# TestPCB_2561.net
KiCad netlist of a schematic drawn in Altium Designer
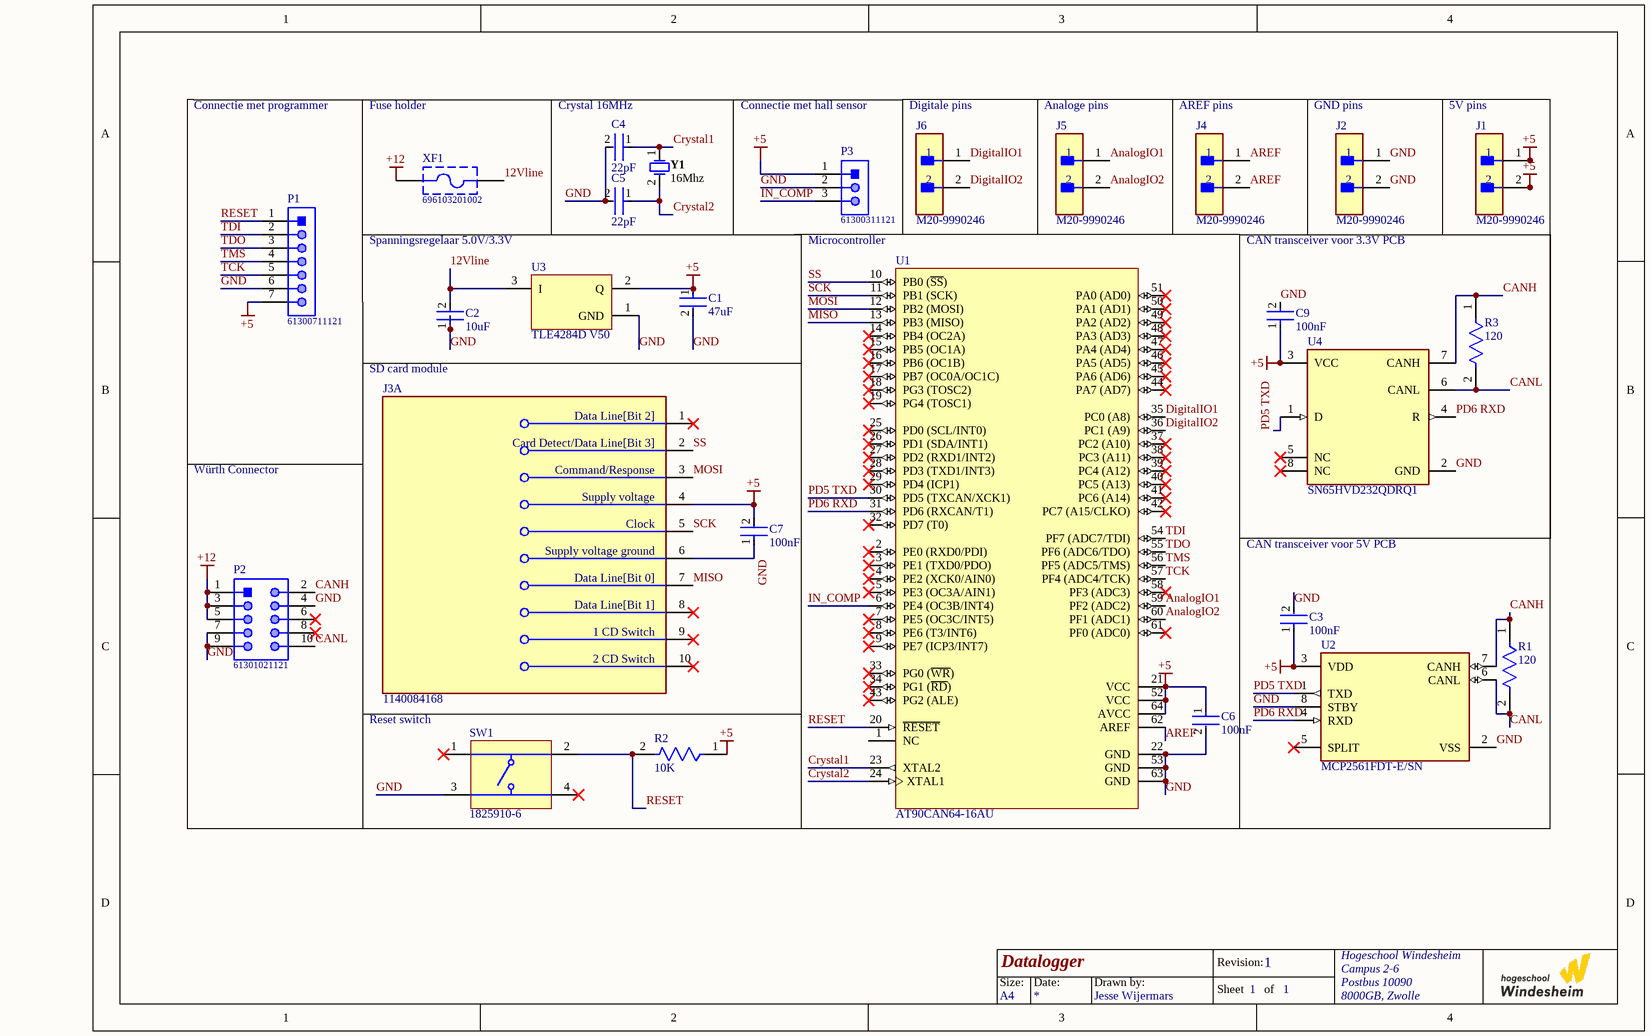
[diagram p0: TestPCB_2561.SchDoc]

(export (version "E")
  (design (tool "Eeschema 10.0.6"))
  (components
    (comp (ref "C1")
      (value "47uF")
      (footprint "FP-CC1206-1_25-MFG")
      (description "CAP CER 0.1UF 50V X7R 1206")
      (fields
        (field (name "OCTOPART") "https://octopart.com/cc1206krx7r9bb104-yageo-39467816")
        (field (name "TOLERANCE") "0.1")
      )
      (libsource (lib "Altium Content Vault") (part "11868f565c42a9108669ba33697ecf6"))
    )
    (comp (ref "C2")
      (value "10uF")
      (footprint "FP-CC1206-1_25-MFG")
      (description "CAP CER 0.1UF 50V X7R 1206")
      (fields
        (field (name "OCTOPART") "https://octopart.com/cc1206krx7r9bb104-yageo-39467816")
        (field (name "TOLERANCE") "0.1")
      )
      (libsource (lib "Altium Content Vault") (part "11868f565c42a9108669ba33697ecf6"))
    )
    (comp (ref "C3")
      (value "100nF")
      (footprint "FP-CC1206-1_25-MFG")
      (description "CAP CER 0.1UF 50V X7R 1206")
      (fields
        (field (name "OCTOPART") "https://octopart.com/cc1206krx7r9bb104-yageo-39467816")
        (field (name "TOLERANCE") "0.1")
      )
      (libsource (lib "Altium Content Vault") (part "11868f565c42a9108669ba33697ecf6"))
    )
    (comp (ref "C4")
      (value "22pF")
      (footprint "FP-CC1206-1_25-MFG")
      (description "CAP CER 0.1UF 50V X7R 1206")
      (fields
        (field (name "OCTOPART") "https://octopart.com/cc1206krx7r9bb104-yageo-39467816")
        (field (name "TOLERANCE") "0.1")
      )
      (libsource (lib "Altium Content Vault") (part "11868f565c42a9108669ba33697ecf6"))
    )
    (comp (ref "C5")
      (value "22pF")
      (footprint "FP-CC1206-1_25-MFG")
      (description "CAP CER 0.1UF 50V X7R 1206")
      (fields
        (field (name "OCTOPART") "https://octopart.com/cc1206krx7r9bb104-yageo-39467816")
        (field (name "TOLERANCE") "0.1")
      )
      (libsource (lib "Altium Content Vault") (part "11868f565c42a9108669ba33697ecf6"))
    )
    (comp (ref "C6")
      (value "100nF")
      (footprint "FP-CC1206-1_25-MFG")
      (description "CAP CER 0.1UF 50V X7R 1206")
      (fields
        (field (name "OCTOPART") "https://octopart.com/cc1206krx7r9bb104-yageo-39467816")
        (field (name "TOLERANCE") "0.1")
      )
      (libsource (lib "Altium Content Vault") (part "11868f565c42a9108669ba33697ecf6"))
    )
    (comp (ref "C7")
      (value "100nF")
      (footprint "FP-CC1206-1_25-MFG")
      (description "CAP CER 0.1UF 50V X7R 1206")
      (fields
        (field (name "OCTOPART") "https://octopart.com/cc1206krx7r9bb104-yageo-39467816")
        (field (name "TOLERANCE") "0.1")
      )
      (libsource (lib "Altium Content Vault") (part "11868f565c42a9108669ba33697ecf6"))
    )
    (comp (ref "C9")
      (value "100nF")
      (footprint "FP-CC1206-1_25-MFG")
      (description "CAP CER 0.1UF 50V X7R 1206")
      (fields
        (field (name "OCTOPART") "https://octopart.com/cc1206krx7r9bb104-yageo-39467816")
        (field (name "TOLERANCE") "0.1")
      )
      (libsource (lib "Altium Content Vault") (part "11868f565c42a9108669ba33697ecf6"))
    )
    (comp (ref "J1")
      (value "M20-9990246")
      (footprint "FP-M20-9990246-MFG")
      (description "CONN HEADER VERT 2POS 2.54MM")
      (fields
        (field (name "OCTOPART") "https://octopart.com/m20-9990246-harwin-2590635")
        (field (name "MANUFACTURER") "Harwin")
      )
      (libsource (lib "Altium Content Vault") (part "3bc925449376181038e59eaffc5286c"))
    )
    (comp (ref "J2")
      (value "M20-9990246")
      (footprint "FP-M20-9990246-MFG")
      (description "CONN HEADER VERT 2POS 2.54MM")
      (fields
        (field (name "OCTOPART") "https://octopart.com/m20-9990246-harwin-2590635")
        (field (name "MANUFACTURER") "Harwin")
      )
      (libsource (lib "Altium Content Vault") (part "3bc925449376181038e59eaffc5286c"))
    )
    (comp (ref "J3")
      (value "1140084168")
      (footprint "FP-1140084168-0")
      (description "CONN MICRO SD CARD PUSH-PULL R/A")
      (libsource (lib "Altium Content Vault") (part "4825e9221753844f043cd0795554885"))
    )
    (comp (ref "J4")
      (value "M20-9990246")
      (footprint "FP-M20-9990246-MFG")
      (description "CONN HEADER VERT 2POS 2.54MM")
      (fields
        (field (name "OCTOPART") "https://octopart.com/m20-9990246-harwin-2590635")
        (field (name "MANUFACTURER") "Harwin")
      )
      (libsource (lib "Altium Content Vault") (part "3bc925449376181038e59eaffc5286c"))
    )
    (comp (ref "J5")
      (value "M20-9990246")
      (footprint "FP-M20-9990246-MFG")
      (description "CONN HEADER VERT 2POS 2.54MM")
      (fields
        (field (name "OCTOPART") "https://octopart.com/m20-9990246-harwin-2590635")
        (field (name "MANUFACTURER") "Harwin")
      )
      (libsource (lib "Altium Content Vault") (part "3bc925449376181038e59eaffc5286c"))
    )
    (comp (ref "J6")
      (value "M20-9990246")
      (footprint "FP-M20-9990246-MFG")
      (description "CONN HEADER VERT 2POS 2.54MM")
      (fields
        (field (name "OCTOPART") "https://octopart.com/m20-9990246-harwin-2590635")
        (field (name "MANUFACTURER") "Harwin")
      )
      (libsource (lib "Altium Content Vault") (part "3bc925449376181038e59eaffc5286c"))
    )
    (comp (ref "P1")
      (value "61300711121")
      (footprint "61300711121")
      (description "THT Vertical Pin Header WR-PHD, Pitch 2.54 mm, Single Row, 7 pins")
      (fields (field (name "MANUFACTURER") "Wurth Elektronik") (field (name "PUBLISHER") "WurthElektronik"))
      (libsource (lib "Altium Content Vault") (part "WE-CN-1P-M-R7"))
    )
    (comp (ref "P2")
      (value "61301021121")
      (footprint "61301021121")
      (description "THT Vertical Pin Header WR-PHD, Pitch 2.54 mm, Dual Row, 10 pins")
      (fields (field (name "MANUFACTURER") "Wurth Elektronik") (field (name "PUBLISHER") "WurthElektronik"))
      (libsource (lib "Altium Content Vault") (part "WE-CN-2P-M-R10"))
    )
    (comp (ref "P3")
      (value "61300311121")
      (footprint "61300311121")
      (description "THT Vertical Pin Header WR-PHD, Pitch 2.54 mm, Single Row, 3 pins")
      (fields (field (name "MANUFACTURER") "Wurth Elektronik") (field (name "PUBLISHER") "WurthElektronik"))
      (libsource (lib "Altium Content Vault") (part "WE-CN-1P-M-R3"))
    )
    (comp (ref "R1")
      (value "120")
      (footprint "FP-CRCW1206-e3-IPC_C")
      (description "RES Thick Film, 0Ω, 0.25W, 1206")
      (fields (field (name "TOLERANCE") "1%"))
      (libsource (lib "Altium Content Vault") (part "1029c3af85768c4190bb7ad29bc67b5"))
    )
    (comp (ref "R2")
      (value "10K")
      (footprint "FP-CRCW1206-e3-IPC_C")
      (description "RES Thick Film, 0Ω, 0.25W, 1206")
      (fields (field (name "TOLERANCE") "1%"))
      (libsource (lib "Altium Content Vault") (part "1029c3af85768c4190bb7ad29bc67b5"))
    )
    (comp (ref "R3")
      (value "120")
      (footprint "FP-CRCW1206-e3-IPC_C")
      (description "RES Thick Film, 0Ω, 0.25W, 1206")
      (fields (field (name "TOLERANCE") "1%"))
      (libsource (lib "Altium Content Vault") (part "1029c3af85768c4190bb7ad29bc67b5"))
    )
    (comp (ref "SW1")
      (value "1825910-6")
      (footprint "TECO-1825910-6_V")
      (description "Tact Switch, SPST-NO, 0.05 A, -35 to 85 degC, 4-Pin THD, RoHS, Bulk")
      (fields (field (name "MANUFACTURER") "TE Connectivity"))
      (libsource (lib "Altium Content Vault") (part "SW-SPST-4_A"))
    )
    (comp (ref "U1")
      (value "AT90CAN64-16AU")
      (footprint "64A_M")
      (libsource (lib "Altium Content Vault") (part "MC-8B-AT90CAN32-SQ64"))
    )
    (comp (ref "U2")
      (value "MCP2561FDT-E/SN")
      (footprint "FP-C04-057-SN-MFG")
      (description "IC TRANSCEIVER 1/1 8SOIC")
      (libsource (lib "Altium Content Vault") (part "d629fcaead47a253bf8bf7df247dcfa"))
    )
    (comp (ref "U3")
      (value "TLE4284D V50")
      (footprint "INF-PG-TO252-3-11_M")
      (description "Voltage Regulator, 6.4 to 40 V Supply, 5 V Output, -40 to 150 degC, PG-TO252-3-11, Reel, Green")
      (fields (field (name "MANUFACTURER") "Infineon"))
      (libsource (lib "Altium Content Vault") (part "INF-TLE4284DVXX-PG-TO252-3-11-3"))
    )
    (comp (ref "U4")
      (value "SN65HVD232QDRQ1")
      (footprint "FP-D0008A-MFG")
      (description "IC TRANSCEIVER HALF 1/1 8SOIC")
      (libsource (lib "Altium Content Vault") (part "3bf20a45497b8b0096c58641b0f280c"))
    )
    (comp (ref "XF1")
      (value "696103201002")
      (footprint "696103201002")
      (description "WR-FSH Fuse Holder Blocks Fuse Holder Blocks Clip Cover for PCB - THR Version")
      (fields (field (name "MANUFACTURER") "Wurth Elektronik") (field (name "PUBLISHER") "WurthElektronik"))
      (libsource (lib "Altium Content Vault") (part "WE-FUSE-2"))
    )
    (comp (ref "Y1")
      (value "16Mhz")
      (footprint "FOX-FOXSLF160-20")
      (description "Resistance Weld Thru-Hole Crystal, 16 MHz, -20 to 70 degC, 2-Pin THD, RoHS, Bulk")
      (fields (field (name "TOLERANCE") "1%"))
      (libsource (lib "Altium Content Vault") (part "XTAL-1-2-2"))
    )
  )
  (nets
    (net (code "1") (name "+5") (class "Default")
      (node (ref "C1") (pin "1") (pinfunction "1_1") (pintype "passive"))
      (node (ref "C3") (pin "1") (pinfunction "1_1") (pintype "passive"))
      (node (ref "C6") (pin "1") (pinfunction "1_1") (pintype "passive"))
      (node (ref "C7") (pin "2") (pinfunction "2_2") (pintype "passive"))
      (node (ref "C9") (pin "1") (pinfunction "1_1") (pintype "passive"))
      (node (ref "J1") (pin "1") (pinfunction "1_1") (pintype "passive"))
      (node (ref "J1") (pin "2") (pinfunction "2_2") (pintype "passive"))
      (node (ref "J3") (pin "4") (pinfunction "Supply_voltage_4") (pintype "passive"))
      (node (ref "P1") (pin "7") (pinfunction "7_7") (pintype "passive"))
      (node (ref "P3") (pin "1") (pinfunction "1_1") (pintype "passive"))
      (node (ref "R2") (pin "1") (pinfunction "1_1") (pintype "passive"))
      (node (ref "U1") (pin "21") (pinfunction "VCC_21") (pintype "power_in"))
      (node (ref "U1") (pin "52") (pinfunction "VCC_52") (pintype "power_in"))
      (node (ref "U1") (pin "64") (pinfunction "AVCC_64") (pintype "power_in"))
      (node (ref "U2") (pin "3") (pinfunction "VDD_3") (pintype "power_in"))
      (node (ref "U3") (pin "2") (pinfunction "Q_2") (pintype "power_in"))
      (node (ref "U4") (pin "3") (pinfunction "VCC_3") (pintype "power_in"))
    )
    (net (code "2") (name "+12") (class "Default")
      (node (ref "P2") (pin "1") (pinfunction "1_1") (pintype "passive"))
      (node (ref "P2") (pin "3") (pinfunction "3_3") (pintype "passive"))
      (node (ref "P2") (pin "5") (pinfunction "5_5") (pintype "passive"))
      (node (ref "XF1") (pin "1") (pinfunction "1_1") (pintype "passive"))
    )
    (net (code "3") (name "/12Vline") (class "Default")
      (node (ref "C2") (pin "2") (pinfunction "2_2") (pintype "passive"))
      (node (ref "U3") (pin "3") (pinfunction "I_3") (pintype "power_in"))
      (node (ref "XF1") (pin "2") (pinfunction "2_2") (pintype "passive"))
    )
    (net (code "5") (name "/AREF") (class "Default")
      (node (ref "J4") (pin "1") (pinfunction "1_1") (pintype "passive"))
      (node (ref "J4") (pin "2") (pinfunction "2_2") (pintype "passive"))
      (node (ref "U1") (pin "62") (pinfunction "AREF_62") (pintype "power_in"))
    )
    (net (code "6") (name "/AnalogIO1") (class "Default")
      (node (ref "J5") (pin "1") (pinfunction "1_1") (pintype "passive"))
      (node (ref "U1") (pin "59") (pinfunction "PF2_(ADC2)_59") (pintype "bidirectional"))
    )
    (net (code "7") (name "/AnalogIO2") (class "Default")
      (node (ref "J5") (pin "2") (pinfunction "2_2") (pintype "passive"))
      (node (ref "U1") (pin "60") (pinfunction "PF1_(ADC1)_60") (pintype "bidirectional"))
    )
    (net (code "8") (name "/CANH") (class "Default")
      (node (ref "P2") (pin "2") (pinfunction "2_2") (pintype "passive"))
      (node (ref "R1") (pin "1") (pinfunction "1_1") (pintype "passive"))
      (node (ref "R3") (pin "1") (pinfunction "1_1") (pintype "passive"))
      (node (ref "U2") (pin "7") (pinfunction "CANH_7") (pintype "bidirectional"))
      (node (ref "U4") (pin "7") (pinfunction "CANH_7") (pintype "passive"))
    )
    (net (code "9") (name "/CANL") (class "Default")
      (node (ref "P2") (pin "10") (pinfunction "10_10") (pintype "passive"))
      (node (ref "R1") (pin "2") (pinfunction "2_2") (pintype "passive"))
      (node (ref "R3") (pin "2") (pinfunction "2_2") (pintype "passive"))
      (node (ref "U2") (pin "6") (pinfunction "CANL_6") (pintype "bidirectional"))
      (node (ref "U4") (pin "6") (pinfunction "CANL_6") (pintype "passive"))
    )
    (net (code "10") (name "/Crystal1") (class "Default")
      (node (ref "C4") (pin "1") (pinfunction "1_1") (pintype "passive"))
      (node (ref "U1") (pin "23") (pinfunction "XTAL2_23") (pintype "output"))
      (node (ref "Y1") (pin "1") (pinfunction "1_1") (pintype "passive"))
    )
    (net (code "11") (name "/Crystal2") (class "Default")
      (node (ref "C5") (pin "1") (pinfunction "1_1") (pintype "passive"))
      (node (ref "U1") (pin "24") (pinfunction "XTAL1_24") (pintype "input"))
      (node (ref "Y1") (pin "2") (pinfunction "2_2") (pintype "passive"))
    )
    (net (code "12") (name "/DigitalIO1") (class "Default")
      (node (ref "J6") (pin "1") (pinfunction "1_1") (pintype "passive"))
      (node (ref "U1") (pin "35") (pinfunction "PC0_(A8)_35") (pintype "bidirectional"))
    )
    (net (code "13") (name "/DigitalIO2") (class "Default")
      (node (ref "J6") (pin "2") (pinfunction "2_2") (pintype "passive"))
      (node (ref "U1") (pin "36") (pinfunction "PC1_(A9)_36") (pintype "bidirectional"))
    )
    (net (code "14") (name "/GND") (class "Default")
      (node (ref "C1") (pin "2") (pinfunction "2_2") (pintype "passive"))
      (node (ref "C2") (pin "1") (pinfunction "1_1") (pintype "passive"))
      (node (ref "C3") (pin "2") (pinfunction "2_2") (pintype "passive"))
      (node (ref "C4") (pin "2") (pinfunction "2_2") (pintype "passive"))
      (node (ref "C5") (pin "2") (pinfunction "2_2") (pintype "passive"))
      (node (ref "C6") (pin "2") (pinfunction "2_2") (pintype "passive"))
      (node (ref "C7") (pin "1") (pinfunction "1_1") (pintype "passive"))
      (node (ref "C9") (pin "2") (pinfunction "2_2") (pintype "passive"))
      (node (ref "J2") (pin "1") (pinfunction "1_1") (pintype "passive"))
      (node (ref "J2") (pin "2") (pinfunction "2_2") (pintype "passive"))
      (node (ref "J3") (pin "6") (pinfunction "Supply_voltage_ground_6") (pintype "passive"))
      (node (ref "P1") (pin "6") (pinfunction "6_6") (pintype "passive"))
      (node (ref "P2") (pin "4") (pinfunction "4_4") (pintype "passive"))
      (node (ref "P2") (pin "7") (pinfunction "7_7") (pintype "passive"))
      (node (ref "P2") (pin "9") (pinfunction "9_9") (pintype "passive"))
      (node (ref "P3") (pin "2") (pinfunction "2_2") (pintype "passive"))
      (node (ref "SW1") (pin "3") (pinfunction "3_3") (pintype "passive"))
      (node (ref "U1") (pin "22") (pinfunction "GND_22") (pintype "power_in"))
      (node (ref "U1") (pin "53") (pinfunction "GND_53") (pintype "power_in"))
      (node (ref "U1") (pin "63") (pinfunction "GND_63") (pintype "power_in"))
      (node (ref "U2") (pin "2") (pinfunction "VSS_2") (pintype "power_in"))
      (node (ref "U2") (pin "8") (pinfunction "STBY_8") (pintype "passive"))
      (node (ref "U3") (pin "1") (pinfunction "GND_1") (pintype "power_in"))
      (node (ref "U4") (pin "2") (pinfunction "GND_2") (pintype "power_in"))
    )
    (net (code "15") (name "/IN_COMP") (class "Default")
      (node (ref "P3") (pin "3") (pinfunction "3_3") (pintype "passive"))
      (node (ref "U1") (pin "6") (pinfunction "PE4_(OC3B/INT4)_6") (pintype "bidirectional"))
    )
    (net (code "16") (name "/MISO") (class "Default")
      (node (ref "J3") (pin "7") (pinfunction "Data_Line[Bit_0]_7") (pintype "passive"))
      (node (ref "U1") (pin "13") (pinfunction "PB3_(MISO)_13") (pintype "bidirectional"))
    )
    (net (code "17") (name "/MOSI") (class "Default")
      (node (ref "J3") (pin "3") (pinfunction "Command/Response_3") (pintype "passive"))
      (node (ref "U1") (pin "12") (pinfunction "PB2_(MOSI)_12") (pintype "bidirectional"))
    )
    (net (code "18") (name "/PD5 TXD") (class "Default")
      (node (ref "U1") (pin "30") (pinfunction "PD5_(TXCAN/XCK1)_30") (pintype "bidirectional"))
      (node (ref "U2") (pin "1") (pinfunction "TXD_1") (pintype "output"))
      (node (ref "U4") (pin "1") (pinfunction "D_1") (pintype "input"))
    )
    (net (code "19") (name "/PD6 RXD") (class "Default")
      (node (ref "U1") (pin "31") (pinfunction "PD6_(RXCAN/T1)_31") (pintype "bidirectional"))
      (node (ref "U2") (pin "4") (pinfunction "RXD_4") (pintype "input"))
      (node (ref "U4") (pin "4") (pinfunction "R_4") (pintype "output"))
    )
    (net (code "20") (name "/RESET") (class "Default")
      (node (ref "P1") (pin "1") (pinfunction "1_1") (pintype "passive"))
      (node (ref "R2") (pin "2") (pinfunction "2_2") (pintype "passive"))
      (node (ref "SW1") (pin "2") (pinfunction "2_2") (pintype "passive"))
      (node (ref "U1") (pin "20") (pinfunction "~{RESET}_20") (pintype "input"))
    )
    (net (code "21") (name "/SCK") (class "Default")
      (node (ref "J3") (pin "5") (pinfunction "Clock_5") (pintype "passive"))
      (node (ref "U1") (pin "11") (pinfunction "PB1_(SCK)_11") (pintype "bidirectional"))
    )
    (net (code "22") (name "/SS") (class "Default")
      (node (ref "J3") (pin "2") (pinfunction "Card_Detect/Data_Line[Bit_3]_2") (pintype "passive"))
      (node (ref "U1") (pin "10") (pinfunction "PB0_(~{SS})_10") (pintype "bidirectional"))
    )
    (net (code "23") (name "/TCK") (class "Default")
      (node (ref "P1") (pin "5") (pinfunction "5_5") (pintype "passive"))
      (node (ref "U1") (pin "57") (pinfunction "PF4_(ADC4/TCK)_57") (pintype "bidirectional"))
    )
    (net (code "24") (name "/TDI") (class "Default")
      (node (ref "P1") (pin "2") (pinfunction "2_2") (pintype "passive"))
      (node (ref "U1") (pin "54") (pinfunction "PF7_(ADC7/TDI)_54") (pintype "bidirectional"))
    )
    (net (code "25") (name "/TDO") (class "Default")
      (node (ref "P1") (pin "3") (pinfunction "3_3") (pintype "passive"))
      (node (ref "U1") (pin "55") (pinfunction "PF6_(ADC6/TDO)_55") (pintype "bidirectional"))
    )
    (net (code "26") (name "/TMS") (class "Default")
      (node (ref "P1") (pin "4") (pinfunction "4_4") (pintype "passive"))
      (node (ref "U1") (pin "56") (pinfunction "PF5_(ADC5/TMS)_56") (pintype "bidirectional"))
    )
    (net (code "27") (name "unconnected-(J3A-1_CD_Switch-Pad9)") (class "Default")
      (node (ref "J3") (pin "9") (pinfunction "1_CD_Switch_9") (pintype "passive+no_connect"))
    )
    (net (code "28") (name "unconnected-(J3A-2_CD_Switch-Pad10)") (class "Default")
      (node (ref "J3") (pin "10") (pinfunction "2_CD_Switch_10") (pintype "passive+no_connect"))
    )
    (net (code "29") (name "unconnected-(J3A-Data_Line[Bit_1]-Pad8)") (class "Default")
      (node (ref "J3") (pin "8") (pinfunction "Data_Line[Bit_1]_8") (pintype "passive+no_connect"))
    )
    (net (code "30") (name "unconnected-(J3A-Data_Line[Bit_2]-Pad1)") (class "Default")
      (node (ref "J3") (pin "1") (pinfunction "Data_Line[Bit_2]_1") (pintype "passive+no_connect"))
    )
    (net (code "31") (name "unconnected-(P2-Pad6)") (class "Default")
      (node (ref "P2") (pin "6") (pinfunction "6_6") (pintype "passive+no_connect"))
    )
    (net (code "32") (name "unconnected-(P2-Pad8)") (class "Default")
      (node (ref "P2") (pin "8") (pinfunction "8_8") (pintype "passive+no_connect"))
    )
    (net (code "33") (name "unconnected-(SW1-Pad1)") (class "Default")
      (node (ref "SW1") (pin "1") (pinfunction "1_1") (pintype "passive+no_connect"))
    )
    (net (code "34") (name "unconnected-(SW1-Pad4)") (class "Default")
      (node (ref "SW1") (pin "4") (pinfunction "4_4") (pintype "passive+no_connect"))
    )
    (net (code "35") (name "unconnected-(U1-NC-Pad1)") (class "Default")
      (node (ref "U1") (pin "1") (pinfunction "NC_1") (pintype "passive"))
    )
    (net (code "36") (name "unconnected-(U1-PA0_(AD0)-Pad51)") (class "Default")
      (node (ref "U1") (pin "51") (pinfunction "PA0_(AD0)_51") (pintype "bidirectional+no_connect"))
    )
    (net (code "37") (name "unconnected-(U1-PA1_(AD1)-Pad50)") (class "Default")
      (node (ref "U1") (pin "50") (pinfunction "PA1_(AD1)_50") (pintype "bidirectional+no_connect"))
    )
    (net (code "38") (name "unconnected-(U1-PA2_(AD2)-Pad49)") (class "Default")
      (node (ref "U1") (pin "49") (pinfunction "PA2_(AD2)_49") (pintype "bidirectional+no_connect"))
    )
    (net (code "39") (name "unconnected-(U1-PA3_(AD3)-Pad48)") (class "Default")
      (node (ref "U1") (pin "48") (pinfunction "PA3_(AD3)_48") (pintype "bidirectional+no_connect"))
    )
    (net (code "40") (name "unconnected-(U1-PA4_(AD4)-Pad47)") (class "Default")
      (node (ref "U1") (pin "47") (pinfunction "PA4_(AD4)_47") (pintype "bidirectional+no_connect"))
    )
    (net (code "41") (name "unconnected-(U1-PA5_(AD5)-Pad46)") (class "Default")
      (node (ref "U1") (pin "46") (pinfunction "PA5_(AD5)_46") (pintype "bidirectional+no_connect"))
    )
    (net (code "42") (name "unconnected-(U1-PA6_(AD6)-Pad45)") (class "Default")
      (node (ref "U1") (pin "45") (pinfunction "PA6_(AD6)_45") (pintype "bidirectional+no_connect"))
    )
    (net (code "43") (name "unconnected-(U1-PA7_(AD7)-Pad44)") (class "Default")
      (node (ref "U1") (pin "44") (pinfunction "PA7_(AD7)_44") (pintype "bidirectional+no_connect"))
    )
    (net (code "44") (name "unconnected-(U1-PB4_(OC2A)-Pad14)") (class "Default")
      (node (ref "U1") (pin "14") (pinfunction "PB4_(OC2A)_14") (pintype "bidirectional+no_connect"))
    )
    (net (code "45") (name "unconnected-(U1-PB5_(OC1A)-Pad15)") (class "Default")
      (node (ref "U1") (pin "15") (pinfunction "PB5_(OC1A)_15") (pintype "bidirectional+no_connect"))
    )
    (net (code "46") (name "unconnected-(U1-PB6_(OC1B)-Pad16)") (class "Default")
      (node (ref "U1") (pin "16") (pinfunction "PB6_(OC1B)_16") (pintype "bidirectional+no_connect"))
    )
    (net (code "47") (name "unconnected-(U1-PB7_(OC0A{slash}OC1C)-Pad17)") (class "Default")
      (node (ref "U1") (pin "17") (pinfunction "PB7_(OC0A/OC1C)_17") (pintype "bidirectional+no_connect"))
    )
    (net (code "48") (name "unconnected-(U1-PC2_(A10)-Pad37)") (class "Default")
      (node (ref "U1") (pin "37") (pinfunction "PC2_(A10)_37") (pintype "bidirectional+no_connect"))
    )
    (net (code "49") (name "unconnected-(U1-PC3_(A11)-Pad38)") (class "Default")
      (node (ref "U1") (pin "38") (pinfunction "PC3_(A11)_38") (pintype "bidirectional+no_connect"))
    )
    (net (code "50") (name "unconnected-(U1-PC4_(A12)-Pad39)") (class "Default")
      (node (ref "U1") (pin "39") (pinfunction "PC4_(A12)_39") (pintype "bidirectional+no_connect"))
    )
    (net (code "51") (name "unconnected-(U1-PC5_(A13)-Pad40)") (class "Default")
      (node (ref "U1") (pin "40") (pinfunction "PC5_(A13)_40") (pintype "bidirectional+no_connect"))
    )
    (net (code "52") (name "unconnected-(U1-PC6_(A14)-Pad41)") (class "Default")
      (node (ref "U1") (pin "41") (pinfunction "PC6_(A14)_41") (pintype "bidirectional+no_connect"))
    )
    (net (code "53") (name "unconnected-(U1-PC7_(A15{slash}CLKO)-Pad42)") (class "Default")
      (node (ref "U1") (pin "42") (pinfunction "PC7_(A15/CLKO)_42") (pintype "bidirectional+no_connect"))
    )
    (net (code "54") (name "unconnected-(U1-PD0_(SCL{slash}INT0)-Pad25)") (class "Default")
      (node (ref "U1") (pin "25") (pinfunction "PD0_(SCL/INT0)_25") (pintype "bidirectional+no_connect"))
    )
    (net (code "55") (name "unconnected-(U1-PD1_(SDA{slash}INT1)-Pad26)") (class "Default")
      (node (ref "U1") (pin "26") (pinfunction "PD1_(SDA/INT1)_26") (pintype "bidirectional+no_connect"))
    )
    (net (code "56") (name "unconnected-(U1-PD2_(RXD1{slash}INT2)-Pad27)") (class "Default")
      (node (ref "U1") (pin "27") (pinfunction "PD2_(RXD1/INT2)_27") (pintype "bidirectional+no_connect"))
    )
    (net (code "57") (name "unconnected-(U1-PD3_(TXD1{slash}INT3)-Pad28)") (class "Default")
      (node (ref "U1") (pin "28") (pinfunction "PD3_(TXD1/INT3)_28") (pintype "bidirectional+no_connect"))
    )
    (net (code "58") (name "unconnected-(U1-PD4_(ICP1)-Pad29)") (class "Default")
      (node (ref "U1") (pin "29") (pinfunction "PD4_(ICP1)_29") (pintype "bidirectional+no_connect"))
    )
    (net (code "59") (name "unconnected-(U1-PD7_(T0)-Pad32)") (class "Default")
      (node (ref "U1") (pin "32") (pinfunction "PD7_(T0)_32") (pintype "bidirectional+no_connect"))
    )
    (net (code "60") (name "unconnected-(U1-PE0_(RXD0{slash}PDI)-Pad2)") (class "Default")
      (node (ref "U1") (pin "2") (pinfunction "PE0_(RXD0/PDI)_2") (pintype "bidirectional+no_connect"))
    )
    (net (code "61") (name "unconnected-(U1-PE1_(TXD0{slash}PDO)-Pad3)") (class "Default")
      (node (ref "U1") (pin "3") (pinfunction "PE1_(TXD0/PDO)_3") (pintype "bidirectional+no_connect"))
    )
    (net (code "62") (name "unconnected-(U1-PE2_(XCK0{slash}AIN0)-Pad4)") (class "Default")
      (node (ref "U1") (pin "4") (pinfunction "PE2_(XCK0/AIN0)_4") (pintype "bidirectional+no_connect"))
    )
    (net (code "63") (name "unconnected-(U1-PE3_(OC3A{slash}AIN1)-Pad5)") (class "Default")
      (node (ref "U1") (pin "5") (pinfunction "PE3_(OC3A/AIN1)_5") (pintype "bidirectional+no_connect"))
    )
    (net (code "64") (name "unconnected-(U1-PE5_(OC3C{slash}INT5)-Pad7)") (class "Default")
      (node (ref "U1") (pin "7") (pinfunction "PE5_(OC3C/INT5)_7") (pintype "bidirectional+no_connect"))
    )
    (net (code "65") (name "unconnected-(U1-PE6_(T3{slash}INT6)-Pad8)") (class "Default")
      (node (ref "U1") (pin "8") (pinfunction "PE6_(T3/INT6)_8") (pintype "bidirectional+no_connect"))
    )
    (net (code "66") (name "unconnected-(U1-PE7_(ICP3{slash}INT7)-Pad9)") (class "Default")
      (node (ref "U1") (pin "9") (pinfunction "PE7_(ICP3/INT7)_9") (pintype "bidirectional+no_connect"))
    )
    (net (code "67") (name "unconnected-(U1-PF0_(ADC0)-Pad61)") (class "Default")
      (node (ref "U1") (pin "61") (pinfunction "PF0_(ADC0)_61") (pintype "bidirectional+no_connect"))
    )
    (net (code "68") (name "unconnected-(U1-PF3_(ADC3)-Pad58)") (class "Default")
      (node (ref "U1") (pin "58") (pinfunction "PF3_(ADC3)_58") (pintype "bidirectional+no_connect"))
    )
    (net (code "69") (name "unconnected-(U1-PG0_(~{WR})-Pad33)") (class "Default")
      (node (ref "U1") (pin "33") (pinfunction "PG0_(~{WR})_33") (pintype "bidirectional+no_connect"))
    )
    (net (code "70") (name "unconnected-(U1-PG1_(~{RD})-Pad34)") (class "Default")
      (node (ref "U1") (pin "34") (pinfunction "PG1_(~{RD})_34") (pintype "bidirectional+no_connect"))
    )
    (net (code "71") (name "unconnected-(U1-PG2_(ALE)-Pad43)") (class "Default")
      (node (ref "U1") (pin "43") (pinfunction "PG2_(ALE)_43") (pintype "bidirectional+no_connect"))
    )
    (net (code "72") (name "unconnected-(U1-PG3_(TOSC2)-Pad18)") (class "Default")
      (node (ref "U1") (pin "18") (pinfunction "PG3_(TOSC2)_18") (pintype "bidirectional+no_connect"))
    )
    (net (code "73") (name "unconnected-(U1-PG4_(TOSC1)-Pad19)") (class "Default")
      (node (ref "U1") (pin "19") (pinfunction "PG4_(TOSC1)_19") (pintype "bidirectional+no_connect"))
    )
    (net (code "74") (name "unconnected-(U2-SPLIT-Pad5)") (class "Default")
      (node (ref "U2") (pin "5") (pinfunction "SPLIT_5") (pintype "passive+no_connect"))
    )
    (net (code "75") (name "unconnected-(U4-NC-Pad5)") (class "Default")
      (node (ref "U4") (pin "5") (pinfunction "NC_5") (pintype "passive+no_connect"))
    )
    (net (code "76") (name "unconnected-(U4-NC-Pad8)") (class "Default")
      (node (ref "U4") (pin "8") (pinfunction "NC_8") (pintype "passive+no_connect"))
    )
  )
)
